# SIM900A_W5500.net
KiCad netlist of a schematic drawn in Altium Designer
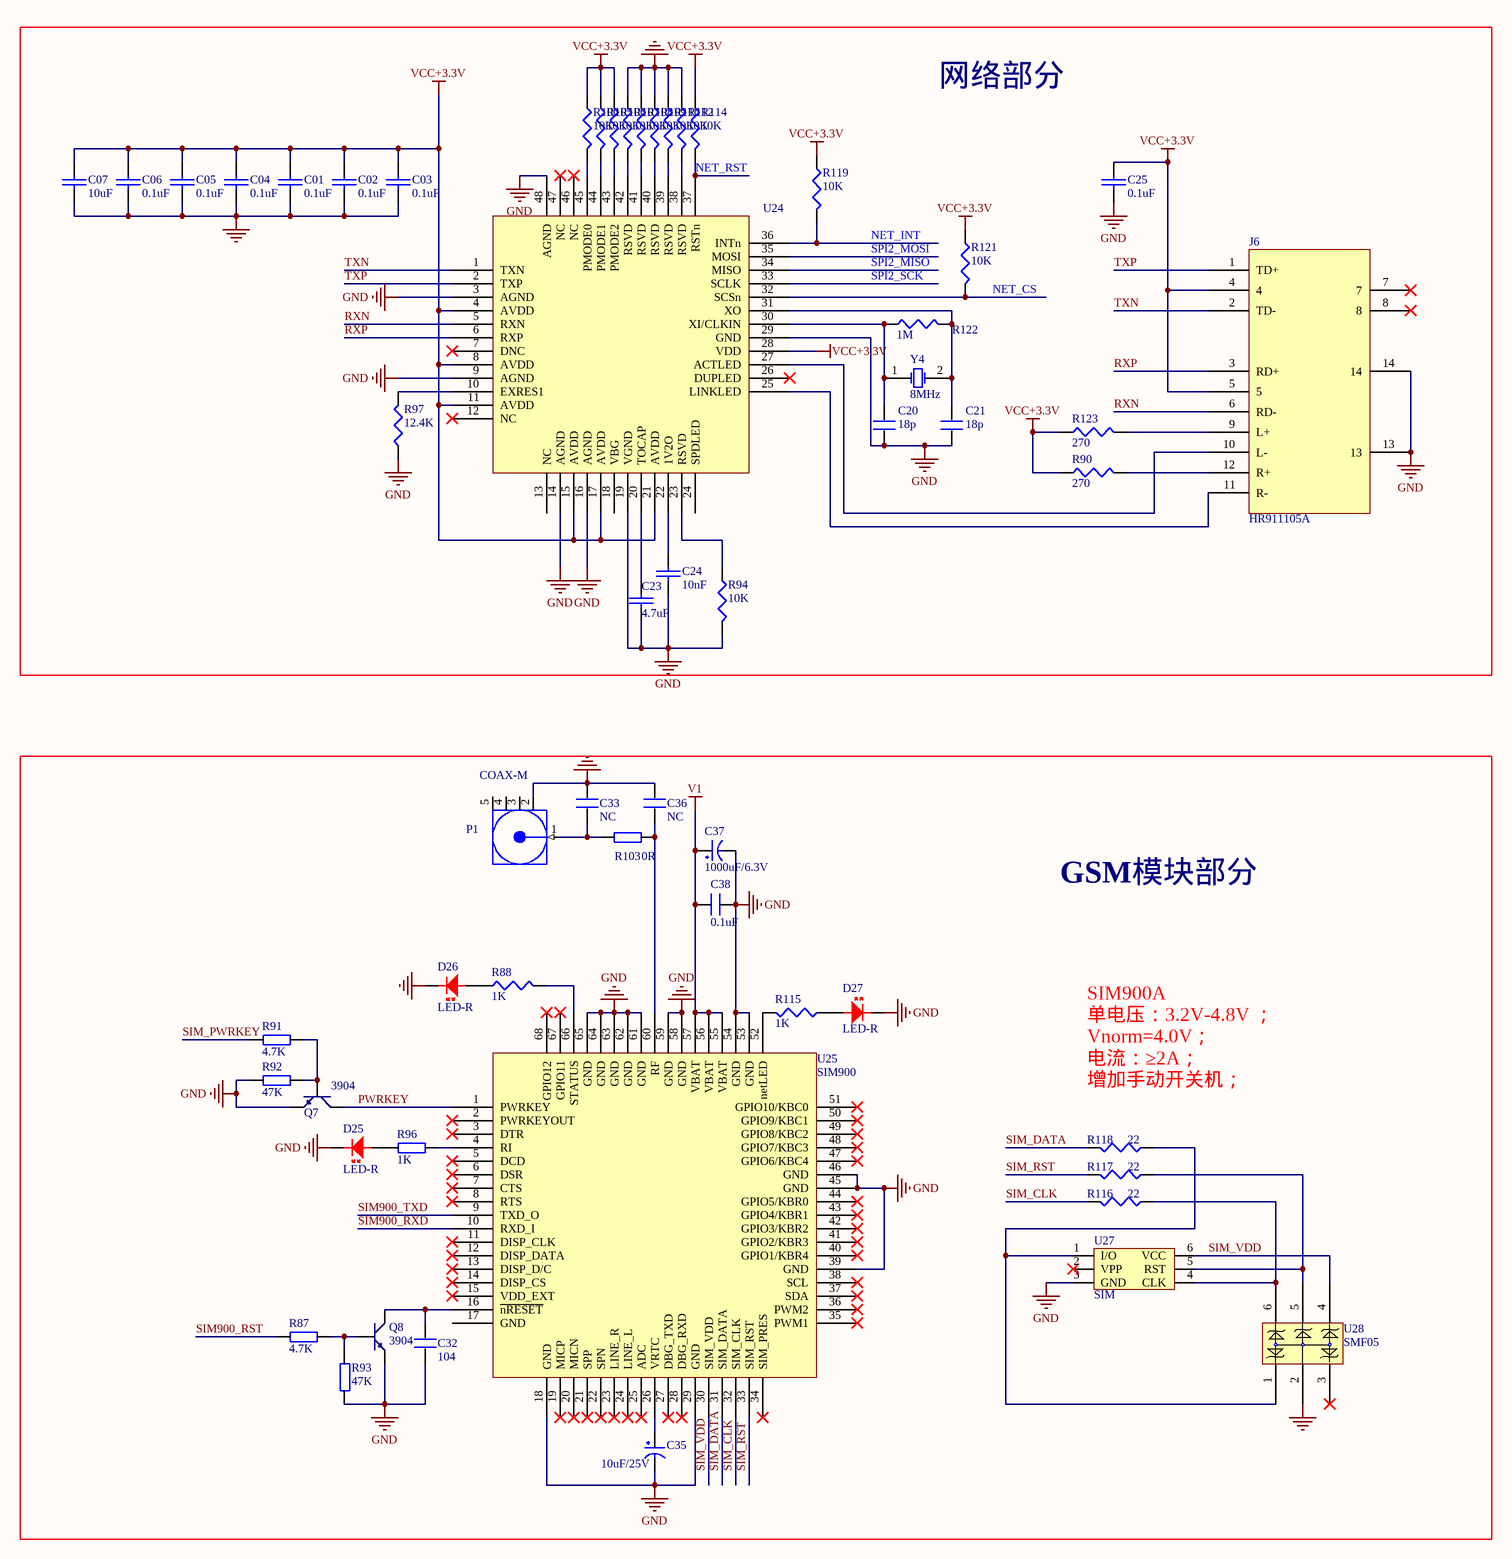
[diagram p0: SIM900A&W5500.SchDoc]

(export (version "E")
  (design (tool "Eeschema 10.0.6"))
  (components
    (comp (ref "C01") (value "0.1uF") (footprint "0603") (libsource (lib "INSPUR_SCH") (part "CAP")))
    (comp (ref "C02") (value "0.1uF") (footprint "0603") (libsource (lib "INSPUR_SCH") (part "CAP")))
    (comp (ref "C03") (value "0.1uF") (footprint "0603") (libsource (lib "INSPUR_SCH") (part "CAP")))
    (comp (ref "C04") (value "0.1uF") (footprint "0603") (libsource (lib "INSPUR_SCH") (part "CAP")))
    (comp (ref "C05") (value "0.1uF") (footprint "0603") (libsource (lib "INSPUR_SCH") (part "CAP")))
    (comp (ref "C06") (value "0.1uF") (footprint "0603") (libsource (lib "INSPUR_SCH") (part "CAP")))
    (comp (ref "C07")
      (value "10uF")
      (footprint "0805")
      (description "0.1uF")
      (libsource (lib "INSPUR_SCH") (part "CAP"))
    )
    (comp (ref "C20") (value "18p") (footprint "0603") (libsource (lib "mylib") (part "C")))
    (comp (ref "C21") (value "18p") (footprint "0603") (libsource (lib "mylib") (part "C")))
    (comp (ref "C23")
      (value "4.7uF")
      (footprint "0603")
      (description "0.1uF")
      (libsource (lib "INSPUR_SCH") (part "CAP"))
    )
    (comp (ref "C24") (value "10nF") (footprint "0603") (libsource (lib "INSPUR_SCH") (part "CAP")))
    (comp (ref "C25") (value "0.1uF") (footprint "0603") (libsource (lib "INSPUR_SCH") (part "CAP")))
    (comp (ref "C32") (value "104") (footprint "0805") (libsource (lib "mylib") (part "C")))
    (comp (ref "C33") (value "NC") (footprint "0805") (libsource (lib "mylib") (part "C")))
    (comp (ref "C35") (value "10uF/25V") (footprint "1206") (libsource (lib "mylib") (part "CAP")))
    (comp (ref "C36") (value "NC") (footprint "0805") (libsource (lib "mylib") (part "C")))
    (comp (ref "C37") (value "1000uF/6.3V") (footprint "7343") (libsource (lib "") (part "CAP_1")))
    (comp (ref "C38") (value "0.1uF") (footprint "0805") (libsource (lib "mylib") (part "C")))
    (comp (ref "D25")
      (value "LED-R")
      (footprint "LED-DIP")
      (description "红色LED")
      (libsource (lib "mylib") (part "LED-RED"))
    )
    (comp (ref "D26")
      (value "LED-R")
      (footprint "LED-DIP")
      (description "红色LED")
      (libsource (lib "mylib") (part "LED-RED"))
    )
    (comp (ref "D27")
      (value "LED-R")
      (footprint "LED-DIP")
      (description "红色LED")
      (libsource (lib "mylib") (part "LED-RED"))
    )
    (comp (ref "J6")
      (value "HR911105A")
      (footprint "HR911105A")
      (libsource (lib "INSPUR_SCH") (part "HR911105A"))
    )
    (comp (ref "P1")
      (value "COAX-M")
      (footprint "ST-TH1")
      (description "SMA-J-P-H-ST-TH1")
      (fields (field (name "PUBLISHER") "Altium Limited"))
      (libsource (lib "Miscellaneous Connectors") (part "COAX-M"))
    )
    (comp (ref "Q7")
      (value "3904")
      (footprint "SOT-23R")
      (description "8050/BCW846/BCW847")
      (libsource (lib "mylib") (part "NPN"))
    )
    (comp (ref "Q8")
      (value "3904")
      (footprint "SOT-23R")
      (description "8050/BCW846/BCW847")
      (libsource (lib "mylib") (part "NPN"))
    )
    (comp (ref "R87") (value "4.7K") (footprint "0805") (libsource (lib "mylib") (part "Res")))
    (comp (ref "R88") (value "1K") (footprint "0805") (libsource (lib "INSPUR_SCH") (part "RES1")))
    (comp (ref "R90") (value "270") (footprint "0603") (libsource (lib "INSPUR_SCH") (part "RES1")))
    (comp (ref "R91") (value "4.7K") (footprint "0805") (libsource (lib "mylib") (part "Res")))
    (comp (ref "R92") (value "47K") (footprint "0805") (libsource (lib "mylib") (part "Res")))
    (comp (ref "R93") (value "47K") (footprint "0805") (libsource (lib "mylib") (part "Res")))
    (comp (ref "R94") (value "10K") (footprint "0603") (libsource (lib "INSPUR_SCH") (part "RES1")))
    (comp (ref "R96") (value "1K") (footprint "0805") (libsource (lib "mylib") (part "Res")))
    (comp (ref "R97") (value "12.4K") (footprint "0603") (libsource (lib "INSPUR_SCH") (part "RES1")))
    (comp (ref "R100") (value "10K") (footprint "0603") (libsource (lib "INSPUR_SCH") (part "RES1")))
    (comp (ref "R103") (value "0R") (footprint "0603") (libsource (lib "mylib") (part "Res")))
    (comp (ref "R105") (value "10K") (footprint "0603") (libsource (lib "INSPUR_SCH") (part "RES1")))
    (comp (ref "R106") (value "10K") (footprint "0603") (libsource (lib "INSPUR_SCH") (part "RES1")))
    (comp (ref "R107") (value "10K") (footprint "0603") (libsource (lib "INSPUR_SCH") (part "RES1")))
    (comp (ref "R108") (value "10K") (footprint "0603") (libsource (lib "INSPUR_SCH") (part "RES1")))
    (comp (ref "R109") (value "10K") (footprint "0603") (libsource (lib "INSPUR_SCH") (part "RES1")))
    (comp (ref "R110") (value "10K") (footprint "0603") (libsource (lib "INSPUR_SCH") (part "RES1")))
    (comp (ref "R112") (value "10K") (footprint "0603") (libsource (lib "INSPUR_SCH") (part "RES1")))
    (comp (ref "R114") (value "10K") (footprint "0603") (libsource (lib "INSPUR_SCH") (part "RES1")))
    (comp (ref "R115") (value "1K") (footprint "0805") (libsource (lib "INSPUR_SCH") (part "RES1")))
    (comp (ref "R116") (value "22") (footprint "0805") (libsource (lib "INSPUR_SCH") (part "RES1")))
    (comp (ref "R117") (value "22") (footprint "0805") (libsource (lib "INSPUR_SCH") (part "RES1")))
    (comp (ref "R118") (value "22") (footprint "0805") (libsource (lib "INSPUR_SCH") (part "RES1")))
    (comp (ref "R119") (value "10K") (footprint "0603") (libsource (lib "INSPUR_SCH") (part "RES1")))
    (comp (ref "R121") (value "10K") (footprint "0603") (libsource (lib "INSPUR_SCH") (part "RES1")))
    (comp (ref "R122") (value "1M") (footprint "0603") (libsource (lib "INSPUR_SCH") (part "RES1")))
    (comp (ref "R123") (value "270") (footprint "0603") (libsource (lib "INSPUR_SCH") (part "RES1")))
    (comp (ref "U24")
      (value "W5500")
      (footprint "LQFP48_N")
      (description "以太网")
      (libsource (lib "mylib") (part "W5500"))
    )
    (comp (ref "U25") (value "SIM900") (footprint "SIM-900") (libsource (lib "ATK-SIM900A") (part "SIM900")))
    (comp (ref "U27")
      (value "SIM")
      (footprint "sim-6p")
      (description "手机SIM卡")
      (libsource (lib "ATK-SIM900A") (part "SIM"))
    )
    (comp (ref "U28") (value "SMF05") (footprint "SC70-6L") (libsource (lib "INSPUR_SCH") (part "SMF05")))
    (comp (ref "Y4")
      (value "8MHz")
      (footprint "XTAL_US")
      (description "Crystal Oscillator")
      (fields (field (name "PUBLISHER") "Altium Limited"))
      (libsource (lib "mylib") (part "XTAL"))
    )
  )
  (nets
    (net (code "1") (name "/NET_CS") (class "Default")
      (node (ref "R121") (pin "2") (pinfunction "2_2") (pintype "passive"))
      (node (ref "U24") (pin "32") (pinfunction "SCSn_32") (pintype "passive"))
    )
    (net (code "2") (name "/NET_INT") (class "Default")
      (node (ref "R119") (pin "2") (pinfunction "2_2") (pintype "passive"))
      (node (ref "U24") (pin "36") (pinfunction "INTn_36") (pintype "passive"))
    )
    (net (code "3") (name "/NET_RST") (class "Default")
      (node (ref "R114") (pin "2") (pinfunction "2_2") (pintype "passive"))
      (node (ref "U24") (pin "37") (pinfunction "RSTn_37") (pintype "passive"))
    )
    (net (code "4") (name "/PWRKEY") (class "Default")
      (node (ref "Q7") (pin "3") (pinfunction "C_3") (pintype "passive"))
      (node (ref "U25") (pin "1") (pinfunction "PWRKEY_1") (pintype "passive"))
    )
    (net (code "5") (name "/RXN") (class "Default")
      (node (ref "J6") (pin "6") (pinfunction "RD-_6") (pintype "passive"))
      (node (ref "U24") (pin "5") (pinfunction "RXN_5") (pintype "passive"))
    )
    (net (code "6") (name "/RXP") (class "Default")
      (node (ref "J6") (pin "3") (pinfunction "RD+_3") (pintype "passive"))
      (node (ref "U24") (pin "6") (pinfunction "RXP_6") (pintype "passive"))
    )
    (net (code "7") (name "/SIM900_RST") (class "Default") (node (ref "R87") (pin "1") (pintype "passive")))
    (net (code "8") (name "/SIM900_RXD") (class "Default")
      (node (ref "U25") (pin "10") (pinfunction "RXD_I_10") (pintype "passive"))
    )
    (net (code "9") (name "/SIM900_TXD") (class "Default")
      (node (ref "U25") (pin "9") (pinfunction "TXD_O_9") (pintype "passive"))
    )
    (net (code "10") (name "/SIM_CLK") (class "Default")
      (node (ref "R116") (pin "2") (pinfunction "2_2") (pintype "passive"))
      (node (ref "U25") (pin "32") (pinfunction "SIM_CLK_32") (pintype "passive"))
    )
    (net (code "11") (name "/SIM_DATA") (class "Default")
      (node (ref "R118") (pin "2") (pinfunction "2_2") (pintype "passive"))
      (node (ref "U25") (pin "31") (pinfunction "SIM_DATA_31") (pintype "passive"))
    )
    (net (code "12") (name "/SIM_PWRKEY") (class "Default") (node (ref "R91") (pin "1") (pintype "passive")))
    (net (code "13") (name "/SIM_RST") (class "Default")
      (node (ref "R117") (pin "2") (pinfunction "2_2") (pintype "passive"))
      (node (ref "U25") (pin "33") (pinfunction "SIM_RST_33") (pintype "passive"))
    )
    (net (code "14") (name "/SIM_VDD") (class "Default")
      (node (ref "U25") (pin "30") (pinfunction "SIM_VDD_30") (pintype "passive"))
      (node (ref "U27") (pin "6") (pinfunction "VCC_6") (pintype "passive"))
      (node (ref "U28") (pin "4") (pintype "passive"))
    )
    (net (code "15") (name "/SPI2_MISO") (class "Default")
      (node (ref "U24") (pin "34") (pinfunction "MISO_34") (pintype "passive"))
    )
    (net (code "16") (name "/SPI2_MOSI") (class "Default")
      (node (ref "U24") (pin "35") (pinfunction "MOSI_35") (pintype "passive"))
    )
    (net (code "17") (name "/SPI2_SCK") (class "Default")
      (node (ref "U24") (pin "33") (pinfunction "SCLK_33") (pintype "passive"))
    )
    (net (code "18") (name "/TXN") (class "Default")
      (node (ref "J6") (pin "2") (pinfunction "TD-_2") (pintype "passive"))
      (node (ref "U24") (pin "1") (pinfunction "TXN_1") (pintype "passive"))
    )
    (net (code "19") (name "/TXP") (class "Default")
      (node (ref "J6") (pin "1") (pinfunction "TD+_1") (pintype "passive"))
      (node (ref "U24") (pin "2") (pinfunction "TXP_2") (pintype "passive"))
    )
    (net (code "20") (name "GND") (class "Default")
      (node (ref "C01") (pin "2") (pinfunction "2_2") (pintype "passive"))
      (node (ref "C02") (pin "2") (pinfunction "2_2") (pintype "passive"))
      (node (ref "C03") (pin "2") (pinfunction "2_2") (pintype "passive"))
      (node (ref "C04") (pin "2") (pinfunction "2_2") (pintype "passive"))
      (node (ref "C05") (pin "2") (pinfunction "2_2") (pintype "passive"))
      (node (ref "C06") (pin "2") (pinfunction "2_2") (pintype "passive"))
      (node (ref "C07") (pin "1") (pinfunction "1_1") (pintype "passive"))
      (node (ref "C20") (pin "1") (pintype "passive"))
      (node (ref "C21") (pin "1") (pintype "passive"))
      (node (ref "C23") (pin "1") (pinfunction "1_1") (pintype "passive"))
      (node (ref "C24") (pin "2") (pinfunction "2_2") (pintype "passive"))
      (node (ref "C25") (pin "2") (pinfunction "2_2") (pintype "passive"))
      (node (ref "C32") (pin "1") (pintype "passive"))
      (node (ref "C33") (pin "2") (pintype "passive"))
      (node (ref "C35") (pin "2") (pinfunction "GND_2") (pintype "passive"))
      (node (ref "C36") (pin "2") (pintype "passive"))
      (node (ref "C37") (pin "2") (pinfunction "GND_2") (pintype "passive"))
      (node (ref "C38") (pin "2") (pintype "passive"))
      (node (ref "D25") (pin "2") (pintype "passive"))
      (node (ref "D26") (pin "2") (pintype "passive"))
      (node (ref "D27") (pin "2") (pintype "passive"))
      (node (ref "J6") (pin "13") (pinfunction "13_13") (pintype "passive"))
      (node (ref "J6") (pin "14") (pinfunction "14_14") (pintype "passive"))
      (node (ref "P1") (pin "2") (pinfunction "GND_2") (pintype "power_in"))
      (node (ref "Q7") (pin "1") (pinfunction "E_1") (pintype "passive"))
      (node (ref "Q8") (pin "1") (pinfunction "E_1") (pintype "passive"))
      (node (ref "R107") (pin "1") (pinfunction "1_1") (pintype "passive"))
      (node (ref "R108") (pin "1") (pinfunction "1_1") (pintype "passive"))
      (node (ref "R109") (pin "1") (pinfunction "1_1") (pintype "passive"))
      (node (ref "R110") (pin "1") (pinfunction "1_1") (pintype "passive"))
      (node (ref "R112") (pin "1") (pinfunction "1_1") (pintype "passive"))
      (node (ref "R92") (pin "1") (pintype "passive"))
      (node (ref "R93") (pin "1") (pintype "passive"))
      (node (ref "R94") (pin "2") (pinfunction "2_2") (pintype "passive"))
      (node (ref "R97") (pin "1") (pinfunction "1_1") (pintype "passive"))
      (node (ref "U24") (pin "14") (pinfunction "AGND_14") (pintype "passive"))
      (node (ref "U24") (pin "16") (pinfunction "AGND_16") (pintype "passive"))
      (node (ref "U24") (pin "19") (pinfunction "VGND_19") (pintype "passive"))
      (node (ref "U24") (pin "29") (pinfunction "GND_29") (pintype "passive"))
      (node (ref "U24") (pin "3") (pinfunction "AGND_3") (pintype "passive"))
      (node (ref "U24") (pin "48") (pinfunction "AGND_48") (pintype "passive"))
      (node (ref "U24") (pin "9") (pinfunction "AGND_9") (pintype "passive"))
      (node (ref "U25") (pin "18") (pinfunction "GND_18") (pintype "passive"))
      (node (ref "U25") (pin "29") (pinfunction "GND_29") (pintype "passive"))
      (node (ref "U25") (pin "39") (pinfunction "GND_39") (pintype "passive"))
      (node (ref "U25") (pin "45") (pinfunction "GND_45") (pintype "passive"))
      (node (ref "U25") (pin "46") (pinfunction "GND_46") (pintype "passive"))
      (node (ref "U25") (pin "53") (pinfunction "GND_53") (pintype "passive"))
      (node (ref "U25") (pin "54") (pinfunction "GND_54") (pintype "passive"))
      (node (ref "U25") (pin "58") (pinfunction "GND_58") (pintype "passive"))
      (node (ref "U25") (pin "59") (pinfunction "GND_59") (pintype "passive"))
      (node (ref "U25") (pin "61") (pinfunction "GND_61") (pintype "passive"))
      (node (ref "U25") (pin "62") (pinfunction "GND_62") (pintype "passive"))
      (node (ref "U25") (pin "63") (pinfunction "GND_63") (pintype "passive"))
      (node (ref "U25") (pin "64") (pinfunction "GND_64") (pintype "passive"))
      (node (ref "U25") (pin "65") (pinfunction "GND_65") (pintype "passive"))
      (node (ref "U27") (pin "3") (pinfunction "GND_3") (pintype "passive"))
      (node (ref "U28") (pin "2") (pintype "passive"))
    )
    (net (code "21") (name "Net-(C35-VCC)") (class "Default")
      (node (ref "C35") (pin "1") (pinfunction "VCC_1") (pintype "passive"))
      (node (ref "U25") (pin "26") (pinfunction "VRTC_26") (pintype "passive"))
    )
    (net (code "22") (name "Net-(D25-Pad1)") (class "Default")
      (node (ref "D25") (pin "1") (pintype "passive"))
      (node (ref "R96") (pin "1") (pintype "passive"))
    )
    (net (code "23") (name "Net-(D26-Pad1)") (class "Default")
      (node (ref "D26") (pin "1") (pintype "passive"))
      (node (ref "R88") (pin "1") (pinfunction "1_1") (pintype "passive"))
    )
    (net (code "24") (name "Net-(D27-Pad1)") (class "Default")
      (node (ref "D27") (pin "1") (pintype "passive"))
      (node (ref "R115") (pin "1") (pinfunction "1_1") (pintype "passive"))
    )
    (net (code "25") (name "Net-(J6-L+)") (class "Default")
      (node (ref "J6") (pin "9") (pinfunction "L+_9") (pintype "passive"))
      (node (ref "R123") (pin "2") (pinfunction "2_2") (pintype "passive"))
    )
    (net (code "26") (name "Net-(J6-L-)") (class "Default")
      (node (ref "J6") (pin "10") (pinfunction "L-_10") (pintype "passive"))
      (node (ref "U24") (pin "27") (pinfunction "ACTLED_27") (pintype "passive"))
    )
    (net (code "27") (name "Net-(J6-R+)") (class "Default")
      (node (ref "J6") (pin "12") (pinfunction "R+_12") (pintype "passive"))
      (node (ref "R90") (pin "2") (pinfunction "2_2") (pintype "passive"))
    )
    (net (code "28") (name "Net-(J6-R-)") (class "Default")
      (node (ref "J6") (pin "11") (pinfunction "R-_11") (pintype "passive"))
      (node (ref "U24") (pin "25") (pinfunction "LINKLED_25") (pintype "passive"))
    )
    (net (code "29") (name "Net-(P1-Signal)") (class "Default")
      (node (ref "C33") (pin "1") (pintype "passive"))
      (node (ref "P1") (pin "1") (pinfunction "Signal_1") (pintype "input"))
      (node (ref "R103") (pin "1") (pintype "passive"))
    )
    (net (code "30") (name "Net-(Q7-B)") (class "Default")
      (node (ref "Q7") (pin "2") (pinfunction "B_2") (pintype "passive"))
      (node (ref "R91") (pin "2") (pintype "passive"))
      (node (ref "R92") (pin "2") (pintype "passive"))
    )
    (net (code "31") (name "Net-(Q8-B)") (class "Default")
      (node (ref "Q8") (pin "2") (pinfunction "B_2") (pintype "passive"))
      (node (ref "R87") (pin "2") (pintype "passive"))
      (node (ref "R93") (pin "2") (pintype "passive"))
    )
    (net (code "32") (name "Net-(Q8-C)") (class "Default")
      (node (ref "C32") (pin "2") (pintype "passive"))
      (node (ref "Q8") (pin "3") (pinfunction "C_3") (pintype "passive"))
      (node (ref "U25") (pin "16") (pinfunction "~{nRESET}_16") (pintype "passive"))
    )
    (net (code "33") (name "Net-(R94-Pad1)") (class "Default")
      (node (ref "R94") (pin "1") (pinfunction "1_1") (pintype "passive"))
      (node (ref "U24") (pin "23") (pinfunction "RSVD_23") (pintype "passive"))
    )
    (net (code "34") (name "Net-(R107-Pad2)") (class "Default")
      (node (ref "R107") (pin "2") (pinfunction "2_2") (pintype "passive"))
      (node (ref "U24") (pin "42") (pinfunction "RSVD_42") (pintype "passive"))
    )
    (net (code "35") (name "Net-(R108-Pad2)") (class "Default")
      (node (ref "R108") (pin "2") (pinfunction "2_2") (pintype "passive"))
      (node (ref "U24") (pin "41") (pinfunction "RSVD_41") (pintype "passive"))
    )
    (net (code "36") (name "Net-(R109-Pad2)") (class "Default")
      (node (ref "R109") (pin "2") (pinfunction "2_2") (pintype "passive"))
      (node (ref "U24") (pin "40") (pinfunction "RSVD_40") (pintype "passive"))
    )
    (net (code "37") (name "Net-(R110-Pad2)") (class "Default")
      (node (ref "R110") (pin "2") (pinfunction "2_2") (pintype "passive"))
      (node (ref "U24") (pin "39") (pinfunction "RSVD_39") (pintype "passive"))
    )
    (net (code "38") (name "Net-(R112-Pad2)") (class "Default")
      (node (ref "R112") (pin "2") (pinfunction "2_2") (pintype "passive"))
      (node (ref "U24") (pin "38") (pinfunction "RSVD_38") (pintype "passive"))
    )
    (net (code "39") (name "Net-(U24-1V2O)") (class "Default")
      (node (ref "C24") (pin "1") (pinfunction "1_1") (pintype "passive"))
      (node (ref "U24") (pin "22") (pinfunction "1V2O_22") (pintype "passive"))
    )
    (net (code "40") (name "Net-(U24-EXRES1)") (class "Default")
      (node (ref "R97") (pin "2") (pinfunction "2_2") (pintype "passive"))
      (node (ref "U24") (pin "10") (pinfunction "EXRES1_10") (pintype "passive"))
    )
    (net (code "41") (name "Net-(U24-PMODE0)") (class "Default")
      (node (ref "R100") (pin "2") (pinfunction "2_2") (pintype "passive"))
      (node (ref "U24") (pin "45") (pinfunction "PMODE0_45") (pintype "passive"))
    )
    (net (code "42") (name "Net-(U24-PMODE1)") (class "Default")
      (node (ref "R105") (pin "2") (pinfunction "2_2") (pintype "passive"))
      (node (ref "U24") (pin "44") (pinfunction "PMODE1_44") (pintype "passive"))
    )
    (net (code "43") (name "Net-(U24-PMODE2)") (class "Default")
      (node (ref "R106") (pin "2") (pinfunction "2_2") (pintype "passive"))
      (node (ref "U24") (pin "43") (pinfunction "PMODE2_43") (pintype "passive"))
    )
    (net (code "44") (name "Net-(U24-TOCAP)") (class "Default")
      (node (ref "C23") (pin "2") (pinfunction "2_2") (pintype "passive"))
      (node (ref "U24") (pin "20") (pinfunction "TOCAP_20") (pintype "passive"))
    )
    (net (code "45") (name "Net-(U24-XI{slash}CLKIN)") (class "Default")
      (node (ref "C20") (pin "2") (pintype "passive"))
      (node (ref "R122") (pin "1") (pinfunction "1_1") (pintype "passive"))
      (node (ref "U24") (pin "30") (pinfunction "XI/CLKIN_30") (pintype "passive"))
      (node (ref "Y4") (pin "1") (pinfunction "OSC1_1") (pintype "passive"))
    )
    (net (code "46") (name "Net-(U24-XO)") (class "Default")
      (node (ref "C21") (pin "2") (pintype "passive"))
      (node (ref "R122") (pin "2") (pinfunction "2_2") (pintype "passive"))
      (node (ref "U24") (pin "31") (pinfunction "XO_31") (pintype "passive"))
      (node (ref "Y4") (pin "2") (pinfunction "OSC2_2") (pintype "passive"))
    )
    (net (code "47") (name "Net-(U25-RF)") (class "Default")
      (node (ref "C36") (pin "1") (pintype "passive"))
      (node (ref "R103") (pin "2") (pintype "passive"))
      (node (ref "U25") (pin "60") (pinfunction "RF_60") (pintype "passive"))
    )
    (net (code "48") (name "Net-(U25-RI)") (class "Default")
      (node (ref "R96") (pin "2") (pintype "passive"))
      (node (ref "U25") (pin "4") (pinfunction "RI_4") (pintype "passive"))
    )
    (net (code "49") (name "Net-(U25-STATUS)") (class "Default")
      (node (ref "R88") (pin "2") (pinfunction "2_2") (pintype "passive"))
      (node (ref "U25") (pin "66") (pinfunction "STATUS_66") (pintype "passive"))
    )
    (net (code "50") (name "Net-(U25-netLED)") (class "Default")
      (node (ref "R115") (pin "2") (pinfunction "2_2") (pintype "passive"))
      (node (ref "U25") (pin "52") (pinfunction "netLED_52") (pintype "passive"))
    )
    (net (code "51") (name "Net-(U27-CLK)") (class "Default")
      (node (ref "R116") (pin "1") (pinfunction "1_1") (pintype "passive"))
      (node (ref "U27") (pin "4") (pinfunction "CLK_4") (pintype "passive"))
      (node (ref "U28") (pin "6") (pintype "passive"))
    )
    (net (code "52") (name "Net-(U27-I{slash}O)") (class "Default")
      (node (ref "R118") (pin "1") (pinfunction "1_1") (pintype "passive"))
      (node (ref "U27") (pin "1") (pinfunction "I/O_1") (pintype "passive"))
      (node (ref "U28") (pin "1") (pintype "passive"))
    )
    (net (code "53") (name "Net-(U27-RST)") (class "Default")
      (node (ref "R117") (pin "1") (pinfunction "1_1") (pintype "passive"))
      (node (ref "U27") (pin "5") (pinfunction "RST_5") (pintype "passive"))
      (node (ref "U28") (pin "5") (pintype "passive"))
    )
    (net (code "54") (name "V1") (class "Default")
      (node (ref "C37") (pin "1") (pinfunction "VCC_1") (pintype "passive"))
      (node (ref "C38") (pin "1") (pintype "passive"))
      (node (ref "U25") (pin "55") (pinfunction "VBAT_55") (pintype "passive"))
      (node (ref "U25") (pin "56") (pinfunction "VBAT_56") (pintype "passive"))
      (node (ref "U25") (pin "57") (pinfunction "VBAT_57") (pintype "passive"))
    )
    (net (code "55") (name "VCC+3.3V") (class "Default")
      (node (ref "C01") (pin "1") (pinfunction "1_1") (pintype "passive"))
      (node (ref "C02") (pin "1") (pinfunction "1_1") (pintype "passive"))
      (node (ref "C03") (pin "1") (pinfunction "1_1") (pintype "passive"))
      (node (ref "C04") (pin "1") (pinfunction "1_1") (pintype "passive"))
      (node (ref "C05") (pin "1") (pinfunction "1_1") (pintype "passive"))
      (node (ref "C06") (pin "1") (pinfunction "1_1") (pintype "passive"))
      (node (ref "C07") (pin "2") (pinfunction "2_2") (pintype "passive"))
      (node (ref "C25") (pin "1") (pinfunction "1_1") (pintype "passive"))
      (node (ref "J6") (pin "4") (pinfunction "4_4") (pintype "passive"))
      (node (ref "J6") (pin "5") (pinfunction "5_5") (pintype "passive"))
      (node (ref "R100") (pin "1") (pinfunction "1_1") (pintype "passive"))
      (node (ref "R105") (pin "1") (pinfunction "1_1") (pintype "passive"))
      (node (ref "R106") (pin "1") (pinfunction "1_1") (pintype "passive"))
      (node (ref "R114") (pin "1") (pinfunction "1_1") (pintype "passive"))
      (node (ref "R119") (pin "1") (pinfunction "1_1") (pintype "passive"))
      (node (ref "R121") (pin "1") (pinfunction "1_1") (pintype "passive"))
      (node (ref "R123") (pin "1") (pinfunction "1_1") (pintype "passive"))
      (node (ref "R90") (pin "1") (pinfunction "1_1") (pintype "passive"))
      (node (ref "U24") (pin "11") (pinfunction "AVDD_11") (pintype "passive"))
      (node (ref "U24") (pin "15") (pinfunction "AVDD_15") (pintype "passive"))
      (node (ref "U24") (pin "17") (pinfunction "AVDD_17") (pintype "passive"))
      (node (ref "U24") (pin "21") (pinfunction "AVDD_21") (pintype "passive"))
      (node (ref "U24") (pin "28") (pinfunction "VDD_28") (pintype "passive"))
      (node (ref "U24") (pin "4") (pinfunction "AVDD_4") (pintype "passive"))
      (node (ref "U24") (pin "8") (pinfunction "AVDD_8") (pintype "passive"))
    )
    (net (code "56") (name "unconnected-(J6-Pad7)") (class "Default")
      (node (ref "J6") (pin "7") (pinfunction "7_7") (pintype "passive+no_connect"))
    )
    (net (code "57") (name "unconnected-(J6-Pad8)") (class "Default")
      (node (ref "J6") (pin "8") (pinfunction "8_8") (pintype "passive+no_connect"))
    )
    (net (code "58") (name "unconnected-(P1-GND-Pad3)") (class "Default")
      (node (ref "P1") (pin "3") (pinfunction "GND_3") (pintype "power_in"))
    )
    (net (code "59") (name "unconnected-(P1-GND-Pad4)") (class "Default")
      (node (ref "P1") (pin "4") (pinfunction "GND_4") (pintype "power_in"))
    )
    (net (code "60") (name "unconnected-(P1-GND-Pad5)") (class "Default")
      (node (ref "P1") (pin "5") (pinfunction "GND_5") (pintype "power_in"))
    )
    (net (code "61") (name "unconnected-(U24-DNC-Pad7)") (class "Default")
      (node (ref "U24") (pin "7") (pinfunction "DNC_7") (pintype "passive+no_connect"))
    )
    (net (code "62") (name "unconnected-(U24-DUPLED-Pad26)") (class "Default")
      (node (ref "U24") (pin "26") (pinfunction "DUPLED_26") (pintype "passive+no_connect"))
    )
    (net (code "63") (name "unconnected-(U24-NC-Pad12)") (class "Default")
      (node (ref "U24") (pin "12") (pinfunction "NC_12") (pintype "passive+no_connect"))
    )
    (net (code "64") (name "unconnected-(U24-NC-Pad13)") (class "Default")
      (node (ref "U24") (pin "13") (pinfunction "NC_13") (pintype "passive"))
    )
    (net (code "65") (name "unconnected-(U24-NC-Pad46)") (class "Default")
      (node (ref "U24") (pin "46") (pinfunction "NC_46") (pintype "passive+no_connect"))
    )
    (net (code "66") (name "unconnected-(U24-NC-Pad47)") (class "Default")
      (node (ref "U24") (pin "47") (pinfunction "NC_47") (pintype "passive+no_connect"))
    )
    (net (code "67") (name "unconnected-(U24-SPDLED-Pad24)") (class "Default")
      (node (ref "U24") (pin "24") (pinfunction "SPDLED_24") (pintype "passive"))
    )
    (net (code "68") (name "unconnected-(U24-VBG-Pad18)") (class "Default")
      (node (ref "U24") (pin "18") (pinfunction "VBG_18") (pintype "passive"))
    )
    (net (code "69") (name "unconnected-(U25-ADC-Pad25)") (class "Default")
      (node (ref "U25") (pin "25") (pinfunction "ADC_25") (pintype "passive+no_connect"))
    )
    (net (code "70") (name "unconnected-(U25-CTS-Pad7)") (class "Default")
      (node (ref "U25") (pin "7") (pinfunction "CTS_7") (pintype "passive+no_connect"))
    )
    (net (code "71") (name "unconnected-(U25-DBG_RXD-Pad28)") (class "Default")
      (node (ref "U25") (pin "28") (pinfunction "DBG_RXD_28") (pintype "passive+no_connect"))
    )
    (net (code "72") (name "unconnected-(U25-DBG_TXD-Pad27)") (class "Default")
      (node (ref "U25") (pin "27") (pinfunction "DBG_TXD_27") (pintype "passive+no_connect"))
    )
    (net (code "73") (name "unconnected-(U25-DCD-Pad5)") (class "Default")
      (node (ref "U25") (pin "5") (pinfunction "DCD_5") (pintype "passive+no_connect"))
    )
    (net (code "74") (name "unconnected-(U25-DISP_CLK-Pad11)") (class "Default")
      (node (ref "U25") (pin "11") (pinfunction "DISP_CLK_11") (pintype "passive+no_connect"))
    )
    (net (code "75") (name "unconnected-(U25-DISP_CS-Pad14)") (class "Default")
      (node (ref "U25") (pin "14") (pinfunction "DISP_CS_14") (pintype "passive+no_connect"))
    )
    (net (code "76") (name "unconnected-(U25-DISP_DATA-Pad12)") (class "Default")
      (node (ref "U25") (pin "12") (pinfunction "DISP_DATA_12") (pintype "passive+no_connect"))
    )
    (net (code "77") (name "unconnected-(U25-DISP_D{slash}C-Pad13)") (class "Default")
      (node (ref "U25") (pin "13") (pinfunction "DISP_D/C_13") (pintype "passive+no_connect"))
    )
    (net (code "78") (name "unconnected-(U25-DSR-Pad6)") (class "Default")
      (node (ref "U25") (pin "6") (pinfunction "DSR_6") (pintype "passive+no_connect"))
    )
    (net (code "79") (name "unconnected-(U25-DTR-Pad3)") (class "Default")
      (node (ref "U25") (pin "3") (pinfunction "DTR_3") (pintype "passive+no_connect"))
    )
    (net (code "80") (name "unconnected-(U25-GND-Pad17)") (class "Default")
      (node (ref "U25") (pin "17") (pinfunction "GND_17") (pintype "passive"))
    )
    (net (code "81") (name "unconnected-(U25-GPIO1{slash}KBR4-Pad40)") (class "Default")
      (node (ref "U25") (pin "40") (pinfunction "GPIO1/KBR4_40") (pintype "passive+no_connect"))
    )
    (net (code "82") (name "unconnected-(U25-GPIO2{slash}KBR3-Pad41)") (class "Default")
      (node (ref "U25") (pin "41") (pinfunction "GPIO2/KBR3_41") (pintype "passive+no_connect"))
    )
    (net (code "83") (name "unconnected-(U25-GPIO3{slash}KBR2-Pad42)") (class "Default")
      (node (ref "U25") (pin "42") (pinfunction "GPIO3/KBR2_42") (pintype "passive+no_connect"))
    )
    (net (code "84") (name "unconnected-(U25-GPIO4{slash}KBR1-Pad43)") (class "Default")
      (node (ref "U25") (pin "43") (pinfunction "GPIO4/KBR1_43") (pintype "passive+no_connect"))
    )
    (net (code "85") (name "unconnected-(U25-GPIO5{slash}KBR0-Pad44)") (class "Default")
      (node (ref "U25") (pin "44") (pinfunction "GPIO5/KBR0_44") (pintype "passive+no_connect"))
    )
    (net (code "86") (name "unconnected-(U25-GPIO6{slash}KBC4-Pad47)") (class "Default")
      (node (ref "U25") (pin "47") (pinfunction "GPIO6/KBC4_47") (pintype "passive+no_connect"))
    )
    (net (code "87") (name "unconnected-(U25-GPIO7{slash}KBC3-Pad48)") (class "Default")
      (node (ref "U25") (pin "48") (pinfunction "GPIO7/KBC3_48") (pintype "passive+no_connect"))
    )
    (net (code "88") (name "unconnected-(U25-GPIO8{slash}KBC2-Pad49)") (class "Default")
      (node (ref "U25") (pin "49") (pinfunction "GPIO8/KBC2_49") (pintype "passive+no_connect"))
    )
    (net (code "89") (name "unconnected-(U25-GPIO9{slash}KBC1-Pad50)") (class "Default")
      (node (ref "U25") (pin "50") (pinfunction "GPIO9/KBC1_50") (pintype "passive+no_connect"))
    )
    (net (code "90") (name "unconnected-(U25-GPIO10{slash}KBC0-Pad51)") (class "Default")
      (node (ref "U25") (pin "51") (pinfunction "GPIO10/KBC0_51") (pintype "passive+no_connect"))
    )
    (net (code "91") (name "unconnected-(U25-GPIO11-Pad67)") (class "Default")
      (node (ref "U25") (pin "67") (pinfunction "GPIO11_67") (pintype "passive+no_connect"))
    )
    (net (code "92") (name "unconnected-(U25-GPIO12-Pad68)") (class "Default")
      (node (ref "U25") (pin "68") (pinfunction "GPIO12_68") (pintype "passive+no_connect"))
    )
    (net (code "93") (name "unconnected-(U25-LINE_L-Pad24)") (class "Default")
      (node (ref "U25") (pin "24") (pinfunction "LINE_L_24") (pintype "passive+no_connect"))
    )
    (net (code "94") (name "unconnected-(U25-LINE_R-Pad23)") (class "Default")
      (node (ref "U25") (pin "23") (pinfunction "LINE_R_23") (pintype "passive+no_connect"))
    )
    (net (code "95") (name "unconnected-(U25-MICN-Pad20)") (class "Default")
      (node (ref "U25") (pin "20") (pinfunction "MICN_20") (pintype "passive+no_connect"))
    )
    (net (code "96") (name "unconnected-(U25-MICP-Pad19)") (class "Default")
      (node (ref "U25") (pin "19") (pinfunction "MICP_19") (pintype "passive+no_connect"))
    )
    (net (code "97") (name "unconnected-(U25-PWM1-Pad35)") (class "Default")
      (node (ref "U25") (pin "35") (pinfunction "PWM1_35") (pintype "passive+no_connect"))
    )
    (net (code "98") (name "unconnected-(U25-PWM2-Pad36)") (class "Default")
      (node (ref "U25") (pin "36") (pinfunction "PWM2_36") (pintype "passive+no_connect"))
    )
    (net (code "99") (name "unconnected-(U25-PWRKEYOUT-Pad2)") (class "Default")
      (node (ref "U25") (pin "2") (pinfunction "PWRKEYOUT_2") (pintype "passive+no_connect"))
    )
    (net (code "100") (name "unconnected-(U25-RTS-Pad8)") (class "Default")
      (node (ref "U25") (pin "8") (pinfunction "RTS_8") (pintype "passive+no_connect"))
    )
    (net (code "101") (name "unconnected-(U25-SCL-Pad38)") (class "Default")
      (node (ref "U25") (pin "38") (pinfunction "SCL_38") (pintype "passive+no_connect"))
    )
    (net (code "102") (name "unconnected-(U25-SDA-Pad37)") (class "Default")
      (node (ref "U25") (pin "37") (pinfunction "SDA_37") (pintype "passive+no_connect"))
    )
    (net (code "103") (name "unconnected-(U25-SIM_PRES-Pad34)") (class "Default")
      (node (ref "U25") (pin "34") (pinfunction "SIM_PRES_34") (pintype "passive+no_connect"))
    )
    (net (code "104") (name "unconnected-(U25-SPN-Pad22)") (class "Default")
      (node (ref "U25") (pin "22") (pinfunction "SPN_22") (pintype "passive+no_connect"))
    )
    (net (code "105") (name "unconnected-(U25-SPP-Pad21)") (class "Default")
      (node (ref "U25") (pin "21") (pinfunction "SPP_21") (pintype "passive+no_connect"))
    )
    (net (code "106") (name "unconnected-(U25-VDD_EXT-Pad15)") (class "Default")
      (node (ref "U25") (pin "15") (pinfunction "VDD_EXT_15") (pintype "passive+no_connect"))
    )
    (net (code "107") (name "unconnected-(U27-VPP-Pad2)") (class "Default")
      (node (ref "U27") (pin "2") (pinfunction "VPP_2") (pintype "passive+no_connect"))
    )
    (net (code "108") (name "unconnected-(U28-Pad3)") (class "Default")
      (node (ref "U28") (pin "3") (pintype "passive+no_connect"))
    )
  )
)
